# lipolski.net
KiCad netlist of a schematic drawn in EAGLE
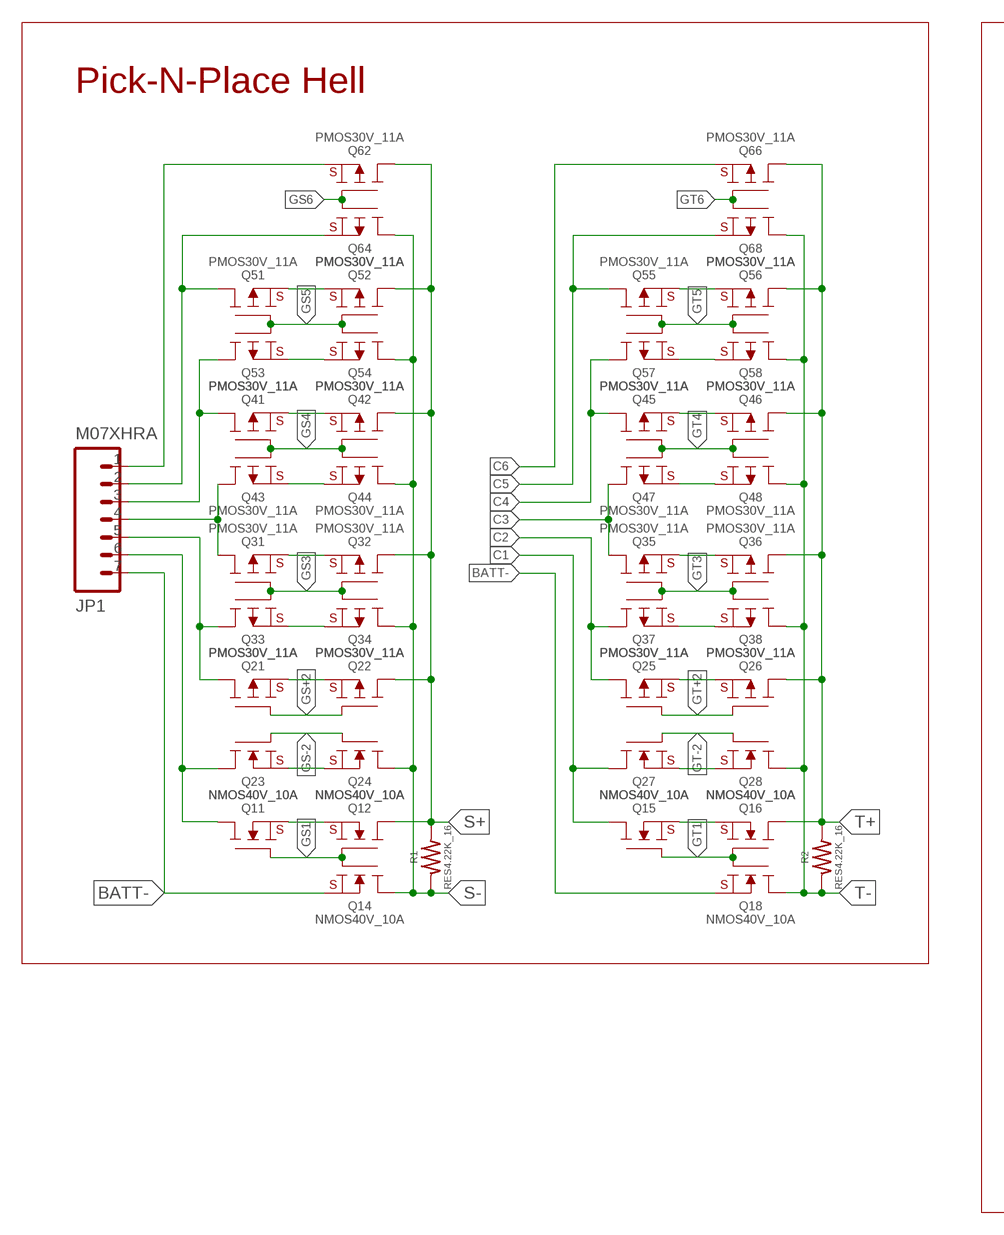
[diagram p0: schematic, sheet 1, part 1 of 2]
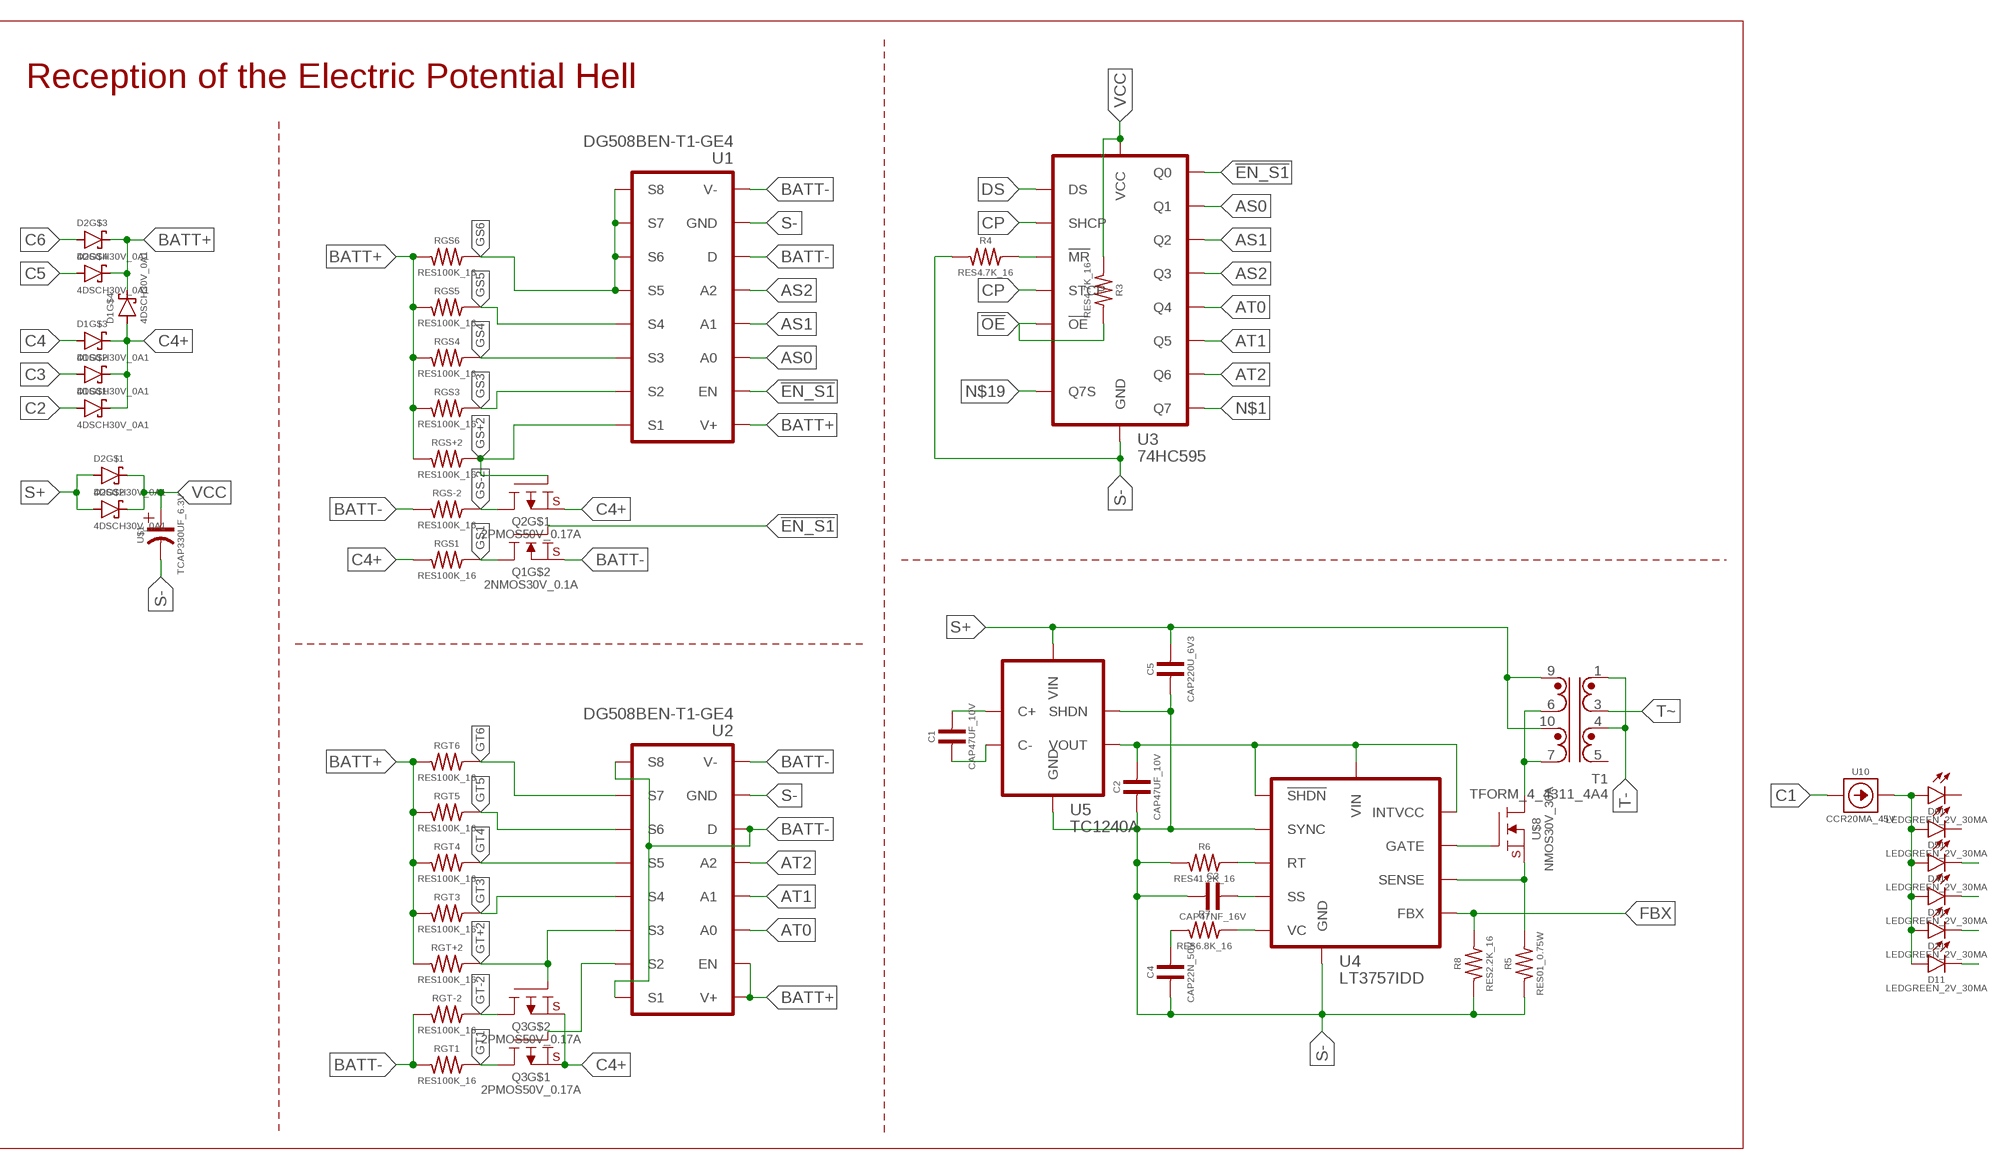
[diagram p1: schematic, sheet 1, part 2 of 2]

(export (version "E")
  (design (tool "Eeschema 10.0.6"))
  (components
    (comp (ref "C1")
      (value "CAP47UF_10V")
      (footprint "eagle-import:0805")
      (fields
        (field (name "DIGIKEY_PART_#") "445-8239-1-ND")
        (field (name "MANUFACTURER") "TDK Corporation")
        (field (name "MFG_PART_#") "C2012X5R1A476M125AC")
      )
      (libsource (lib "eagle-import") (part "CAP47UF_10V"))
    )
    (comp (ref "C2")
      (value "CAP47UF_10V")
      (footprint "eagle-import:0805")
      (fields
        (field (name "DIGIKEY_PART_#") "445-8239-1-ND")
        (field (name "MANUFACTURER") "TDK Corporation")
        (field (name "MFG_PART_#") "C2012X5R1A476M125AC")
      )
      (libsource (lib "eagle-import") (part "CAP47UF_10V"))
    )
    (comp (ref "C3")
      (value "CAP47NF_16V")
      (footprint "eagle-import:0201P")
      (fields
        (field (name "DIGIKEY_PART_#") "587-1225-1-ND")
        (field (name "MANUFACTURER") "Taiyo Yuden")
        (field (name "MFG_PART_#") "EMK105B7473KV-F")
      )
      (libsource (lib "eagle-import") (part "CAP47NF_16V"))
    )
    (comp (ref "C4")
      (value "CAP22N_50V")
      (footprint "eagle-import:0402")
      (fields
        (field (name "DIGIKEY_PART_#") "490-3884-1-ND")
        (field (name "MANUFACTURER") "Murata Electronics North America")
        (field (name "MFG_PART_#") "GRM155R71H223KA12D")
      )
      (libsource (lib "eagle-import") (part "CAP22N_50V"))
    )
    (comp (ref "C5")
      (value "CAP220U_6V3")
      (footprint "eagle-import:1210")
      (fields
        (field (name "DIGIKEY_PART_#") "1276-3375-1-ND")
        (field (name "MANUFACTURER") "Samsung Electro-Mechanics America, Inc.")
        (field (name "MFG_PART_#") "CL32A227MQVNNNE")
      )
      (libsource (lib "eagle-import") (part "CAP220U_6V3"))
    )
    (comp (ref "D1")
      (value "4DSCH30V_0A1")
      (footprint "eagle-import:8-HMD")
      (fields
        (field (name "DIGIKEY_PART_#") "RB521ZS8A30TE61CT-ND")
        (field (name "MANUFACTURER") "Rohm Semiconductor")
        (field (name "MFG_PART_#") "RB521ZS8A30TE61")
      )
      (libsource (lib "eagle-import") (part "4DSCH30V_0A1"))
    )
    (comp (ref "D2")
      (value "4DSCH30V_0A1")
      (footprint "eagle-import:8-HMD")
      (fields
        (field (name "DIGIKEY_PART_#") "RB521ZS8A30TE61CT-ND")
        (field (name "MANUFACTURER") "Rohm Semiconductor")
        (field (name "MFG_PART_#") "RB521ZS8A30TE61")
      )
      (libsource (lib "eagle-import") (part "4DSCH30V_0A1"))
    )
    (comp (ref "D11")
      (value "LEDGREEN_2V_30MA")
      (footprint "eagle-import:0603+")
      (fields
        (field (name "DIGIKEY_PART_#") "160-1435-1-ND")
        (field (name "MANUFACTURER") "Lite-On Inc.")
        (field (name "MFG_PART_#") "LTST-C190KGKT")
      )
      (libsource (lib "eagle-import") (part "LEDGREEN_2V_30MA"))
    )
    (comp (ref "D21")
      (value "LEDGREEN_2V_30MA")
      (footprint "eagle-import:0603+")
      (fields
        (field (name "DIGIKEY_PART_#") "160-1435-1-ND")
        (field (name "MANUFACTURER") "Lite-On Inc.")
        (field (name "MFG_PART_#") "LTST-C190KGKT")
      )
      (libsource (lib "eagle-import") (part "LEDGREEN_2V_30MA"))
    )
    (comp (ref "D31")
      (value "LEDGREEN_2V_30MA")
      (footprint "eagle-import:0603+")
      (fields
        (field (name "DIGIKEY_PART_#") "160-1435-1-ND")
        (field (name "MANUFACTURER") "Lite-On Inc.")
        (field (name "MFG_PART_#") "LTST-C190KGKT")
      )
      (libsource (lib "eagle-import") (part "LEDGREEN_2V_30MA"))
    )
    (comp (ref "D41")
      (value "LEDGREEN_2V_30MA")
      (footprint "eagle-import:0603+")
      (fields
        (field (name "DIGIKEY_PART_#") "160-1435-1-ND")
        (field (name "MANUFACTURER") "Lite-On Inc.")
        (field (name "MFG_PART_#") "LTST-C190KGKT")
      )
      (libsource (lib "eagle-import") (part "LEDGREEN_2V_30MA"))
    )
    (comp (ref "D51")
      (value "LEDGREEN_2V_30MA")
      (footprint "eagle-import:0603+")
      (fields
        (field (name "DIGIKEY_PART_#") "160-1435-1-ND")
        (field (name "MANUFACTURER") "Lite-On Inc.")
        (field (name "MFG_PART_#") "LTST-C190KGKT")
      )
      (libsource (lib "eagle-import") (part "LEDGREEN_2V_30MA"))
    )
    (comp (ref "D61")
      (value "LEDGREEN_2V_30MA")
      (footprint "eagle-import:0603+")
      (fields
        (field (name "DIGIKEY_PART_#") "160-1435-1-ND")
        (field (name "MANUFACTURER") "Lite-On Inc.")
        (field (name "MFG_PART_#") "LTST-C190KGKT")
      )
      (libsource (lib "eagle-import") (part "LEDGREEN_2V_30MA"))
    )
    (comp (ref "JP1")
      (value "M07XHRA")
      (footprint "eagle-import:XH07-RA")
      (fields
        (field (name "DIGIKEY_PART_#") "455-2240-ND")
        (field (name "MANUFACTURER") "JST Sales America Inc.")
        (field (name "MFG_PART_#") "S7B-XH-A(LF)(SN)")
      )
      (libsource (lib "eagle-import") (part "M07XHRA"))
    )
    (comp (ref "Q1")
      (value "2NMOS30V_0.1A")
      (footprint "eagle-import:SOT-666")
      (fields
        (field (name "DIGIKEY_PART_#") "FC6943010RCT-ND")
        (field (name "MANUFACTURER") "Panasonic Electronic Components")
        (field (name "MFG_PART_#") "FC6943010R")
      )
      (libsource (lib "eagle-import") (part "2NMOS30V_0.1A"))
    )
    (comp (ref "Q2")
      (value "2PMOS50V_0.17A")
      (footprint "eagle-import:SOT-666")
      (fields
        (field (name "DIGIKEY_PART_#") "568-10474-1-ND")
        (field (name "MANUFACTURER") "NXP Semiconductors")
        (field (name "MFG_PART_#") "BSS84AKV,115")
      )
      (libsource (lib "eagle-import") (part "2PMOS50V_0.17A"))
    )
    (comp (ref "Q3")
      (value "2PMOS50V_0.17A")
      (footprint "eagle-import:SOT-666")
      (fields
        (field (name "DIGIKEY_PART_#") "568-10474-1-ND")
        (field (name "MANUFACTURER") "NXP Semiconductors")
        (field (name "MFG_PART_#") "BSS84AKV,115")
      )
      (libsource (lib "eagle-import") (part "2PMOS50V_0.17A"))
    )
    (comp (ref "Q11")
      (value "NMOS40V_10A")
      (footprint "eagle-import:6-POWERWDFN")
      (fields
        (field (name "DIGIKEY_PART_#") "FDMA7670CT-ND")
        (field (name "MANUFACTURER") "Fairchild Semiconductor")
        (field (name "MFG_PART_#") "FDMA7670")
      )
      (libsource (lib "eagle-import") (part "NMOS40V_10A"))
    )
    (comp (ref "Q12")
      (value "NMOS40V_10A")
      (footprint "eagle-import:6-POWERWDFN")
      (fields
        (field (name "DIGIKEY_PART_#") "FDMA7670CT-ND")
        (field (name "MANUFACTURER") "Fairchild Semiconductor")
        (field (name "MFG_PART_#") "FDMA7670")
      )
      (libsource (lib "eagle-import") (part "NMOS40V_10A"))
    )
    (comp (ref "Q14")
      (value "NMOS40V_10A")
      (footprint "eagle-import:6-POWERWDFN")
      (fields
        (field (name "DIGIKEY_PART_#") "FDMA7670CT-ND")
        (field (name "MANUFACTURER") "Fairchild Semiconductor")
        (field (name "MFG_PART_#") "FDMA7670")
      )
      (libsource (lib "eagle-import") (part "NMOS40V_10A"))
    )
    (comp (ref "Q15")
      (value "NMOS40V_10A")
      (footprint "eagle-import:6-POWERWDFN")
      (fields
        (field (name "DIGIKEY_PART_#") "FDMA7670CT-ND")
        (field (name "MANUFACTURER") "Fairchild Semiconductor")
        (field (name "MFG_PART_#") "FDMA7670")
      )
      (libsource (lib "eagle-import") (part "NMOS40V_10A"))
    )
    (comp (ref "Q16")
      (value "NMOS40V_10A")
      (footprint "eagle-import:6-POWERWDFN")
      (fields
        (field (name "DIGIKEY_PART_#") "FDMA7670CT-ND")
        (field (name "MANUFACTURER") "Fairchild Semiconductor")
        (field (name "MFG_PART_#") "FDMA7670")
      )
      (libsource (lib "eagle-import") (part "NMOS40V_10A"))
    )
    (comp (ref "Q18")
      (value "NMOS40V_10A")
      (footprint "eagle-import:6-POWERWDFN")
      (fields
        (field (name "DIGIKEY_PART_#") "FDMA7670CT-ND")
        (field (name "MANUFACTURER") "Fairchild Semiconductor")
        (field (name "MFG_PART_#") "FDMA7670")
      )
      (libsource (lib "eagle-import") (part "NMOS40V_10A"))
    )
    (comp (ref "Q21")
      (value "PMOS30V_11A")
      (footprint "eagle-import:6-POWERWDFN")
      (fields
        (field (name "DIGIKEY_PART_#") "FDMA6676PZCT-ND")
        (field (name "MANUFACTURER") "Fairchild Semiconductor")
        (field (name "MFG_PART_#") "FDMA6676PZ")
      )
      (libsource (lib "eagle-import") (part "PMOS30V_11A"))
    )
    (comp (ref "Q22")
      (value "PMOS30V_11A")
      (footprint "eagle-import:6-POWERWDFN")
      (fields
        (field (name "DIGIKEY_PART_#") "FDMA6676PZCT-ND")
        (field (name "MANUFACTURER") "Fairchild Semiconductor")
        (field (name "MFG_PART_#") "FDMA6676PZ")
      )
      (libsource (lib "eagle-import") (part "PMOS30V_11A"))
    )
    (comp (ref "Q23")
      (value "NMOS40V_10A")
      (footprint "eagle-import:6-POWERWDFN")
      (fields
        (field (name "DIGIKEY_PART_#") "FDMA7670CT-ND")
        (field (name "MANUFACTURER") "Fairchild Semiconductor")
        (field (name "MFG_PART_#") "FDMA7670")
      )
      (libsource (lib "eagle-import") (part "NMOS40V_10A"))
    )
    (comp (ref "Q24")
      (value "NMOS40V_10A")
      (footprint "eagle-import:6-POWERWDFN")
      (fields
        (field (name "DIGIKEY_PART_#") "FDMA7670CT-ND")
        (field (name "MANUFACTURER") "Fairchild Semiconductor")
        (field (name "MFG_PART_#") "FDMA7670")
      )
      (libsource (lib "eagle-import") (part "NMOS40V_10A"))
    )
    (comp (ref "Q25")
      (value "PMOS30V_11A")
      (footprint "eagle-import:6-POWERWDFN")
      (fields
        (field (name "DIGIKEY_PART_#") "FDMA6676PZCT-ND")
        (field (name "MANUFACTURER") "Fairchild Semiconductor")
        (field (name "MFG_PART_#") "FDMA6676PZ")
      )
      (libsource (lib "eagle-import") (part "PMOS30V_11A"))
    )
    (comp (ref "Q26")
      (value "PMOS30V_11A")
      (footprint "eagle-import:6-POWERWDFN")
      (fields
        (field (name "DIGIKEY_PART_#") "FDMA6676PZCT-ND")
        (field (name "MANUFACTURER") "Fairchild Semiconductor")
        (field (name "MFG_PART_#") "FDMA6676PZ")
      )
      (libsource (lib "eagle-import") (part "PMOS30V_11A"))
    )
    (comp (ref "Q27")
      (value "NMOS40V_10A")
      (footprint "eagle-import:6-POWERWDFN")
      (fields
        (field (name "DIGIKEY_PART_#") "FDMA7670CT-ND")
        (field (name "MANUFACTURER") "Fairchild Semiconductor")
        (field (name "MFG_PART_#") "FDMA7670")
      )
      (libsource (lib "eagle-import") (part "NMOS40V_10A"))
    )
    (comp (ref "Q28")
      (value "NMOS40V_10A")
      (footprint "eagle-import:6-POWERWDFN")
      (fields
        (field (name "DIGIKEY_PART_#") "FDMA7670CT-ND")
        (field (name "MANUFACTURER") "Fairchild Semiconductor")
        (field (name "MFG_PART_#") "FDMA7670")
      )
      (libsource (lib "eagle-import") (part "NMOS40V_10A"))
    )
    (comp (ref "Q31")
      (value "PMOS30V_11A")
      (footprint "eagle-import:6-POWERWDFN")
      (fields
        (field (name "DIGIKEY_PART_#") "FDMA6676PZCT-ND")
        (field (name "MANUFACTURER") "Fairchild Semiconductor")
        (field (name "MFG_PART_#") "FDMA6676PZ")
      )
      (libsource (lib "eagle-import") (part "PMOS30V_11A"))
    )
    (comp (ref "Q32")
      (value "PMOS30V_11A")
      (footprint "eagle-import:6-POWERWDFN")
      (fields
        (field (name "DIGIKEY_PART_#") "FDMA6676PZCT-ND")
        (field (name "MANUFACTURER") "Fairchild Semiconductor")
        (field (name "MFG_PART_#") "FDMA6676PZ")
      )
      (libsource (lib "eagle-import") (part "PMOS30V_11A"))
    )
    (comp (ref "Q33")
      (value "PMOS30V_11A")
      (footprint "eagle-import:6-POWERWDFN")
      (fields
        (field (name "DIGIKEY_PART_#") "FDMA6676PZCT-ND")
        (field (name "MANUFACTURER") "Fairchild Semiconductor")
        (field (name "MFG_PART_#") "FDMA6676PZ")
      )
      (libsource (lib "eagle-import") (part "PMOS30V_11A"))
    )
    (comp (ref "Q34")
      (value "PMOS30V_11A")
      (footprint "eagle-import:6-POWERWDFN")
      (fields
        (field (name "DIGIKEY_PART_#") "FDMA6676PZCT-ND")
        (field (name "MANUFACTURER") "Fairchild Semiconductor")
        (field (name "MFG_PART_#") "FDMA6676PZ")
      )
      (libsource (lib "eagle-import") (part "PMOS30V_11A"))
    )
    (comp (ref "Q35")
      (value "PMOS30V_11A")
      (footprint "eagle-import:6-POWERWDFN")
      (fields
        (field (name "DIGIKEY_PART_#") "FDMA6676PZCT-ND")
        (field (name "MANUFACTURER") "Fairchild Semiconductor")
        (field (name "MFG_PART_#") "FDMA6676PZ")
      )
      (libsource (lib "eagle-import") (part "PMOS30V_11A"))
    )
    (comp (ref "Q36")
      (value "PMOS30V_11A")
      (footprint "eagle-import:6-POWERWDFN")
      (fields
        (field (name "DIGIKEY_PART_#") "FDMA6676PZCT-ND")
        (field (name "MANUFACTURER") "Fairchild Semiconductor")
        (field (name "MFG_PART_#") "FDMA6676PZ")
      )
      (libsource (lib "eagle-import") (part "PMOS30V_11A"))
    )
    (comp (ref "Q37")
      (value "PMOS30V_11A")
      (footprint "eagle-import:6-POWERWDFN")
      (fields
        (field (name "DIGIKEY_PART_#") "FDMA6676PZCT-ND")
        (field (name "MANUFACTURER") "Fairchild Semiconductor")
        (field (name "MFG_PART_#") "FDMA6676PZ")
      )
      (libsource (lib "eagle-import") (part "PMOS30V_11A"))
    )
    (comp (ref "Q38")
      (value "PMOS30V_11A")
      (footprint "eagle-import:6-POWERWDFN")
      (fields
        (field (name "DIGIKEY_PART_#") "FDMA6676PZCT-ND")
        (field (name "MANUFACTURER") "Fairchild Semiconductor")
        (field (name "MFG_PART_#") "FDMA6676PZ")
      )
      (libsource (lib "eagle-import") (part "PMOS30V_11A"))
    )
    (comp (ref "Q41")
      (value "PMOS30V_11A")
      (footprint "eagle-import:6-POWERWDFN")
      (fields
        (field (name "DIGIKEY_PART_#") "FDMA6676PZCT-ND")
        (field (name "MANUFACTURER") "Fairchild Semiconductor")
        (field (name "MFG_PART_#") "FDMA6676PZ")
      )
      (libsource (lib "eagle-import") (part "PMOS30V_11A"))
    )
    (comp (ref "Q42")
      (value "PMOS30V_11A")
      (footprint "eagle-import:6-POWERWDFN")
      (fields
        (field (name "DIGIKEY_PART_#") "FDMA6676PZCT-ND")
        (field (name "MANUFACTURER") "Fairchild Semiconductor")
        (field (name "MFG_PART_#") "FDMA6676PZ")
      )
      (libsource (lib "eagle-import") (part "PMOS30V_11A"))
    )
    (comp (ref "Q43")
      (value "PMOS30V_11A")
      (footprint "eagle-import:6-POWERWDFN")
      (fields
        (field (name "DIGIKEY_PART_#") "FDMA6676PZCT-ND")
        (field (name "MANUFACTURER") "Fairchild Semiconductor")
        (field (name "MFG_PART_#") "FDMA6676PZ")
      )
      (libsource (lib "eagle-import") (part "PMOS30V_11A"))
    )
    (comp (ref "Q44")
      (value "PMOS30V_11A")
      (footprint "eagle-import:6-POWERWDFN")
      (fields
        (field (name "DIGIKEY_PART_#") "FDMA6676PZCT-ND")
        (field (name "MANUFACTURER") "Fairchild Semiconductor")
        (field (name "MFG_PART_#") "FDMA6676PZ")
      )
      (libsource (lib "eagle-import") (part "PMOS30V_11A"))
    )
    (comp (ref "Q45")
      (value "PMOS30V_11A")
      (footprint "eagle-import:6-POWERWDFN")
      (fields
        (field (name "DIGIKEY_PART_#") "FDMA6676PZCT-ND")
        (field (name "MANUFACTURER") "Fairchild Semiconductor")
        (field (name "MFG_PART_#") "FDMA6676PZ")
      )
      (libsource (lib "eagle-import") (part "PMOS30V_11A"))
    )
    (comp (ref "Q46")
      (value "PMOS30V_11A")
      (footprint "eagle-import:6-POWERWDFN")
      (fields
        (field (name "DIGIKEY_PART_#") "FDMA6676PZCT-ND")
        (field (name "MANUFACTURER") "Fairchild Semiconductor")
        (field (name "MFG_PART_#") "FDMA6676PZ")
      )
      (libsource (lib "eagle-import") (part "PMOS30V_11A"))
    )
    (comp (ref "Q47")
      (value "PMOS30V_11A")
      (footprint "eagle-import:6-POWERWDFN")
      (fields
        (field (name "DIGIKEY_PART_#") "FDMA6676PZCT-ND")
        (field (name "MANUFACTURER") "Fairchild Semiconductor")
        (field (name "MFG_PART_#") "FDMA6676PZ")
      )
      (libsource (lib "eagle-import") (part "PMOS30V_11A"))
    )
    (comp (ref "Q48")
      (value "PMOS30V_11A")
      (footprint "eagle-import:6-POWERWDFN")
      (fields
        (field (name "DIGIKEY_PART_#") "FDMA6676PZCT-ND")
        (field (name "MANUFACTURER") "Fairchild Semiconductor")
        (field (name "MFG_PART_#") "FDMA6676PZ")
      )
      (libsource (lib "eagle-import") (part "PMOS30V_11A"))
    )
    (comp (ref "Q51")
      (value "PMOS30V_11A")
      (footprint "eagle-import:6-POWERWDFN")
      (fields
        (field (name "DIGIKEY_PART_#") "FDMA6676PZCT-ND")
        (field (name "MANUFACTURER") "Fairchild Semiconductor")
        (field (name "MFG_PART_#") "FDMA6676PZ")
      )
      (libsource (lib "eagle-import") (part "PMOS30V_11A"))
    )
    (comp (ref "Q52")
      (value "PMOS30V_11A")
      (footprint "eagle-import:6-POWERWDFN")
      (fields
        (field (name "DIGIKEY_PART_#") "FDMA6676PZCT-ND")
        (field (name "MANUFACTURER") "Fairchild Semiconductor")
        (field (name "MFG_PART_#") "FDMA6676PZ")
      )
      (libsource (lib "eagle-import") (part "PMOS30V_11A"))
    )
    (comp (ref "Q53")
      (value "PMOS30V_11A")
      (footprint "eagle-import:6-POWERWDFN")
      (fields
        (field (name "DIGIKEY_PART_#") "FDMA6676PZCT-ND")
        (field (name "MANUFACTURER") "Fairchild Semiconductor")
        (field (name "MFG_PART_#") "FDMA6676PZ")
      )
      (libsource (lib "eagle-import") (part "PMOS30V_11A"))
    )
    (comp (ref "Q54")
      (value "PMOS30V_11A")
      (footprint "eagle-import:6-POWERWDFN")
      (fields
        (field (name "DIGIKEY_PART_#") "FDMA6676PZCT-ND")
        (field (name "MANUFACTURER") "Fairchild Semiconductor")
        (field (name "MFG_PART_#") "FDMA6676PZ")
      )
      (libsource (lib "eagle-import") (part "PMOS30V_11A"))
    )
    (comp (ref "Q55")
      (value "PMOS30V_11A")
      (footprint "eagle-import:6-POWERWDFN")
      (fields
        (field (name "DIGIKEY_PART_#") "FDMA6676PZCT-ND")
        (field (name "MANUFACTURER") "Fairchild Semiconductor")
        (field (name "MFG_PART_#") "FDMA6676PZ")
      )
      (libsource (lib "eagle-import") (part "PMOS30V_11A"))
    )
    (comp (ref "Q56")
      (value "PMOS30V_11A")
      (footprint "eagle-import:6-POWERWDFN")
      (fields
        (field (name "DIGIKEY_PART_#") "FDMA6676PZCT-ND")
        (field (name "MANUFACTURER") "Fairchild Semiconductor")
        (field (name "MFG_PART_#") "FDMA6676PZ")
      )
      (libsource (lib "eagle-import") (part "PMOS30V_11A"))
    )
    (comp (ref "Q57")
      (value "PMOS30V_11A")
      (footprint "eagle-import:6-POWERWDFN")
      (fields
        (field (name "DIGIKEY_PART_#") "FDMA6676PZCT-ND")
        (field (name "MANUFACTURER") "Fairchild Semiconductor")
        (field (name "MFG_PART_#") "FDMA6676PZ")
      )
      (libsource (lib "eagle-import") (part "PMOS30V_11A"))
    )
    (comp (ref "Q58")
      (value "PMOS30V_11A")
      (footprint "eagle-import:6-POWERWDFN")
      (fields
        (field (name "DIGIKEY_PART_#") "FDMA6676PZCT-ND")
        (field (name "MANUFACTURER") "Fairchild Semiconductor")
        (field (name "MFG_PART_#") "FDMA6676PZ")
      )
      (libsource (lib "eagle-import") (part "PMOS30V_11A"))
    )
    (comp (ref "Q62")
      (value "PMOS30V_11A")
      (footprint "eagle-import:6-POWERWDFN")
      (fields
        (field (name "DIGIKEY_PART_#") "FDMA6676PZCT-ND")
        (field (name "MANUFACTURER") "Fairchild Semiconductor")
        (field (name "MFG_PART_#") "FDMA6676PZ")
      )
      (libsource (lib "eagle-import") (part "PMOS30V_11A"))
    )
    (comp (ref "Q64")
      (value "PMOS30V_11A")
      (footprint "eagle-import:6-POWERWDFN")
      (fields
        (field (name "DIGIKEY_PART_#") "FDMA6676PZCT-ND")
        (field (name "MANUFACTURER") "Fairchild Semiconductor")
        (field (name "MFG_PART_#") "FDMA6676PZ")
      )
      (libsource (lib "eagle-import") (part "PMOS30V_11A"))
    )
    (comp (ref "Q66")
      (value "PMOS30V_11A")
      (footprint "eagle-import:6-POWERWDFN")
      (fields
        (field (name "DIGIKEY_PART_#") "FDMA6676PZCT-ND")
        (field (name "MANUFACTURER") "Fairchild Semiconductor")
        (field (name "MFG_PART_#") "FDMA6676PZ")
      )
      (libsource (lib "eagle-import") (part "PMOS30V_11A"))
    )
    (comp (ref "Q68")
      (value "PMOS30V_11A")
      (footprint "eagle-import:6-POWERWDFN")
      (fields
        (field (name "DIGIKEY_PART_#") "FDMA6676PZCT-ND")
        (field (name "MANUFACTURER") "Fairchild Semiconductor")
        (field (name "MFG_PART_#") "FDMA6676PZ")
      )
      (libsource (lib "eagle-import") (part "PMOS30V_11A"))
    )
    (comp (ref "R1")
      (value "RES4.22K_16")
      (footprint "eagle-import:0402")
      (fields
        (field (name "DIGIKEY_PART_#") "541-4.22KLCT-ND")
        (field (name "MANUFACTURER") "Vishay Dale")
        (field (name "MFG_PART_#") "CRCW04024K22FKED")
      )
      (libsource (lib "eagle-import") (part "RES4.22K_16"))
    )
    (comp (ref "R2")
      (value "RES4.22K_16")
      (footprint "eagle-import:0402")
      (fields
        (field (name "DIGIKEY_PART_#") "541-4.22KLCT-ND")
        (field (name "MANUFACTURER") "Vishay Dale")
        (field (name "MFG_PART_#") "CRCW04024K22FKED")
      )
      (libsource (lib "eagle-import") (part "RES4.22K_16"))
    )
    (comp (ref "R3")
      (value "RES4.7K_16")
      (footprint "eagle-import:0402")
      (fields
        (field (name "DIGIKEY_PART_#") "541-4.70KLCT-ND")
        (field (name "MANUFACTURER") "Vishay Dale")
        (field (name "MFG_PART_#") "CRCW04024K70FKED")
      )
      (libsource (lib "eagle-import") (part "RES4.7K_16"))
    )
    (comp (ref "R4")
      (value "RES4.7K_16")
      (footprint "eagle-import:0402")
      (fields
        (field (name "DIGIKEY_PART_#") "541-4.70KLCT-ND")
        (field (name "MANUFACTURER") "Vishay Dale")
        (field (name "MFG_PART_#") "CRCW04024K70FKED")
      )
      (libsource (lib "eagle-import") (part "RES4.7K_16"))
    )
    (comp (ref "R5")
      (value "RES01_0.75W")
      (footprint "eagle-import:1206")
      (fields
        (field (name "DIGIKEY_PART_#") "408-1570-1-ND")
        (field (name "MANUFACTURER") "Susumu")
        (field (name "MFG_PART_#") "KRL1632E-M-R010-F-T5")
      )
      (libsource (lib "eagle-import") (part "RES01_0.75W"))
    )
    (comp (ref "R6")
      (value "RES41.2K_16")
      (footprint "eagle-import:0402")
      (fields
        (field (name "DIGIKEY_PART_#") "541-41.2KLCT-ND")
        (field (name "MANUFACTURER") "Vishay Dale")
        (field (name "MFG_PART_#") "CRCW040241K2FKED")
      )
      (libsource (lib "eagle-import") (part "RES41.2K_16"))
    )
    (comp (ref "R7")
      (value "RES6.8K_16")
      (footprint "eagle-import:0402")
      (fields
        (field (name "DIGIKEY_PART_#") "541-6.80KLCT-ND")
        (field (name "MANUFACTURER") "Vishay Dale")
        (field (name "MFG_PART_#") "CRCW04026K80FKED")
      )
      (libsource (lib "eagle-import") (part "RES6.8K_16"))
    )
    (comp (ref "R8")
      (value "RES2.2K_16")
      (footprint "eagle-import:0402")
      (fields
        (field (name "DIGIKEY_PART_#") "541-2.20KLCT-ND")
        (field (name "MANUFACTURER") "Vishay Dale")
        (field (name "MFG_PART_#") "CRCW04022K20FKED")
      )
      (libsource (lib "eagle-import") (part "RES2.2K_16"))
    )
    (comp (ref "RGS+2")
      (value "RES100K_16")
      (footprint "eagle-import:0402")
      (fields
        (field (name "DIGIKEY_PART_#") "541-100KLCT-ND")
        (field (name "MANUFACTURER") "Vishay Dale")
        (field (name "MFG_PART_#") "CRCW0402100KFKED")
      )
      (libsource (lib "eagle-import") (part "RES100K_16"))
    )
    (comp (ref "RGS-2")
      (value "RES100K_16")
      (footprint "eagle-import:0402")
      (fields
        (field (name "DIGIKEY_PART_#") "541-100KLCT-ND")
        (field (name "MANUFACTURER") "Vishay Dale")
        (field (name "MFG_PART_#") "CRCW0402100KFKED")
      )
      (libsource (lib "eagle-import") (part "RES100K_16"))
    )
    (comp (ref "RGS1")
      (value "RES100K_16")
      (footprint "eagle-import:0402")
      (fields
        (field (name "DIGIKEY_PART_#") "541-100KLCT-ND")
        (field (name "MANUFACTURER") "Vishay Dale")
        (field (name "MFG_PART_#") "CRCW0402100KFKED")
      )
      (libsource (lib "eagle-import") (part "RES100K_16"))
    )
    (comp (ref "RGS3")
      (value "RES100K_16")
      (footprint "eagle-import:0402")
      (fields
        (field (name "DIGIKEY_PART_#") "541-100KLCT-ND")
        (field (name "MANUFACTURER") "Vishay Dale")
        (field (name "MFG_PART_#") "CRCW0402100KFKED")
      )
      (libsource (lib "eagle-import") (part "RES100K_16"))
    )
    (comp (ref "RGS4")
      (value "RES100K_16")
      (footprint "eagle-import:0402")
      (fields
        (field (name "DIGIKEY_PART_#") "541-100KLCT-ND")
        (field (name "MANUFACTURER") "Vishay Dale")
        (field (name "MFG_PART_#") "CRCW0402100KFKED")
      )
      (libsource (lib "eagle-import") (part "RES100K_16"))
    )
    (comp (ref "RGS5")
      (value "RES100K_16")
      (footprint "eagle-import:0402")
      (fields
        (field (name "DIGIKEY_PART_#") "541-100KLCT-ND")
        (field (name "MANUFACTURER") "Vishay Dale")
        (field (name "MFG_PART_#") "CRCW0402100KFKED")
      )
      (libsource (lib "eagle-import") (part "RES100K_16"))
    )
    (comp (ref "RGS6")
      (value "RES100K_16")
      (footprint "eagle-import:0402")
      (fields
        (field (name "DIGIKEY_PART_#") "541-100KLCT-ND")
        (field (name "MANUFACTURER") "Vishay Dale")
        (field (name "MFG_PART_#") "CRCW0402100KFKED")
      )
      (libsource (lib "eagle-import") (part "RES100K_16"))
    )
    (comp (ref "RGT+2")
      (value "RES100K_16")
      (footprint "eagle-import:0402")
      (fields
        (field (name "DIGIKEY_PART_#") "541-100KLCT-ND")
        (field (name "MANUFACTURER") "Vishay Dale")
        (field (name "MFG_PART_#") "CRCW0402100KFKED")
      )
      (libsource (lib "eagle-import") (part "RES100K_16"))
    )
    (comp (ref "RGT-2")
      (value "RES100K_16")
      (footprint "eagle-import:0402")
      (fields
        (field (name "DIGIKEY_PART_#") "541-100KLCT-ND")
        (field (name "MANUFACTURER") "Vishay Dale")
        (field (name "MFG_PART_#") "CRCW0402100KFKED")
      )
      (libsource (lib "eagle-import") (part "RES100K_16"))
    )
    (comp (ref "RGT1")
      (value "RES100K_16")
      (footprint "eagle-import:0402")
      (fields
        (field (name "DIGIKEY_PART_#") "541-100KLCT-ND")
        (field (name "MANUFACTURER") "Vishay Dale")
        (field (name "MFG_PART_#") "CRCW0402100KFKED")
      )
      (libsource (lib "eagle-import") (part "RES100K_16"))
    )
    (comp (ref "RGT3")
      (value "RES100K_16")
      (footprint "eagle-import:0402")
      (fields
        (field (name "DIGIKEY_PART_#") "541-100KLCT-ND")
        (field (name "MANUFACTURER") "Vishay Dale")
        (field (name "MFG_PART_#") "CRCW0402100KFKED")
      )
      (libsource (lib "eagle-import") (part "RES100K_16"))
    )
    (comp (ref "RGT4")
      (value "RES100K_16")
      (footprint "eagle-import:0402")
      (fields
        (field (name "DIGIKEY_PART_#") "541-100KLCT-ND")
        (field (name "MANUFACTURER") "Vishay Dale")
        (field (name "MFG_PART_#") "CRCW0402100KFKED")
      )
      (libsource (lib "eagle-import") (part "RES100K_16"))
    )
    (comp (ref "RGT5")
      (value "RES100K_16")
      (footprint "eagle-import:0402")
      (fields
        (field (name "DIGIKEY_PART_#") "541-100KLCT-ND")
        (field (name "MANUFACTURER") "Vishay Dale")
        (field (name "MFG_PART_#") "CRCW0402100KFKED")
      )
      (libsource (lib "eagle-import") (part "RES100K_16"))
    )
    (comp (ref "RGT6")
      (value "RES100K_16")
      (footprint "eagle-import:0402")
      (fields
        (field (name "DIGIKEY_PART_#") "541-100KLCT-ND")
        (field (name "MANUFACTURER") "Vishay Dale")
        (field (name "MFG_PART_#") "CRCW0402100KFKED")
      )
      (libsource (lib "eagle-import") (part "RES100K_16"))
    )
    (comp (ref "T1")
      (value "TFORM_4_4311_4A4")
      (footprint "eagle-import:EPQ13")
      (fields
        (field (name "DIGIKEY_PART_#") "732-6198-1-ND")
        (field (name "MANUFACTURER") "Wurth Electronics Inc")
        (field (name "MFG_PART_#") "7491195501")
      )
      (libsource (lib "eagle-import") (part "TFORM_4_4311_4A4"))
    )
    (comp (ref "U$1")
      (value "TCAP330UF_6.3V")
      (footprint "eagle-import:1210+")
      (fields
        (field (name "DIGIKEY_PART_#") "478-8407-1-ND")
        (field (name "MANUFACTURER") "AVX Corporation")
        (field (name "MFG_PART_#") "F950J337KBAAQ2")
      )
      (libsource (lib "eagle-import") (part "TCAP330UF_6.3V"))
    )
    (comp (ref "U$8")
      (value "NMOS30V_30A")
      (footprint "eagle-import:8-POWERWDFN")
      (fields
        (field (name "DIGIKEY_PART_#") "FDMC8010ET30CT-ND")
        (field (name "MANUFACTURER") "Fairchild Semiconductor")
        (field (name "MFG_PART_#") "FDMC8010ET30")
      )
      (libsource (lib "eagle-import") (part "NMOS30V_30A"))
    )
    (comp (ref "U1")
      (value "DG508BEN-T1-GE4")
      (footprint "eagle-import:MINIQFN-16L")
      (fields
        (field (name "MANUFACTURER") "Vishay Siliconix")
        (field (name "MOUSER_PART_#") "78-DG508BEN-T1-GE4")
      )
      (libsource (lib "eagle-import") (part "DG508BEN-T1-GE4"))
    )
    (comp (ref "U2")
      (value "DG508BEN-T1-GE4")
      (footprint "eagle-import:MINIQFN-16L")
      (fields
        (field (name "MANUFACTURER") "Vishay Siliconix")
        (field (name "MOUSER_PART_#") "78-DG508BEN-T1-GE4")
      )
      (libsource (lib "eagle-import") (part "DG508BEN-T1-GE4"))
    )
    (comp (ref "U3")
      (value "74HC595")
      (footprint "eagle-import:16-VFQFN")
      (fields
        (field (name "DIGIKEY_PART_#") "568-2719-1-ND")
        (field (name "MANUFACTURER") "NXP Semiconductors")
        (field (name "MFG_PART_#") "74HC595BQ,115")
      )
      (libsource (lib "eagle-import") (part "74HC595"))
    )
    (comp (ref "U4")
      (value "LT3757IDD")
      (footprint "eagle-import:10-WFDFN")
      (fields
        (field (name "DIGIKEY_PART_#") "LT3757IDD#PBF-ND")
        (field (name "MANUFACTURER") "Linear Technology")
        (field (name "MFG_PART_#") "LT3757IDD#PBF")
      )
      (libsource (lib "eagle-import") (part "LT3757IDD"))
    )
    (comp (ref "U5")
      (value "TC1240A")
      (footprint "eagle-import:SOT-23-6")
      (fields
        (field (name "DIGIKEY_PART_#") "TC1240AECHCT-ND")
        (field (name "MANUFACTURER") "Microchip Technology")
        (field (name "MFG_PART_#") "TC1240AECHTR")
      )
      (libsource (lib "eagle-import") (part "TC1240A"))
    )
    (comp (ref "U10")
      (value "CCR20MA_45V")
      (footprint "eagle-import:SOD-123")
      (fields
        (field (name "DIGIKEY_PART_#") "NSI45020T1GOSCT-ND")
        (field (name "MANUFACTURER") "ON Semiconductor")
        (field (name "MFG_PART_#") "NSI45020T1G")
      )
      (libsource (lib "eagle-import") (part "CCR20MA_45V"))
    )
  )
  (nets
    (net (code "1") (name "/T~{}") (class "Default")
      (node (ref "T1") (pin "3") (pinfunction "2_3") (pintype "passive"))
    )
    (net (code "2") (name "/~{EN_S1}") (class "Default")
      (node (ref "Q1") (pin "5") (pinfunction "G_5") (pintype "passive"))
      (node (ref "U1") (pin "16") (pinfunction "EN_16") (pintype "passive"))
      (node (ref "U3") (pin "15") (pinfunction "Q0_15") (pintype "passive"))
    )
    (net (code "3") (name "/~{OE}") (class "Default")
      (node (ref "R3") (pin "2") (pinfunction "2_2") (pintype "passive"))
      (node (ref "U3") (pin "13") (pinfunction "~{OE}_13") (pintype "passive"))
    )
    (net (code "4") (name "AS0") (class "Default")
      (node (ref "U1") (pin "15") (pinfunction "A0_15") (pintype "passive"))
      (node (ref "U3") (pin "1") (pinfunction "Q1_1") (pintype "passive"))
    )
    (net (code "5") (name "AS1") (class "Default")
      (node (ref "U1") (pin "14") (pinfunction "A1_14") (pintype "passive"))
      (node (ref "U3") (pin "2") (pinfunction "Q2_2") (pintype "passive"))
    )
    (net (code "6") (name "AS2") (class "Default")
      (node (ref "U1") (pin "13") (pinfunction "A2_13") (pintype "passive"))
      (node (ref "U3") (pin "3") (pinfunction "Q3_3") (pintype "passive"))
    )
    (net (code "7") (name "AT0") (class "Default")
      (node (ref "U2") (pin "15") (pinfunction "A0_15") (pintype "passive"))
      (node (ref "U3") (pin "4") (pinfunction "Q4_4") (pintype "passive"))
    )
    (net (code "8") (name "AT1") (class "Default")
      (node (ref "U2") (pin "14") (pinfunction "A1_14") (pintype "passive"))
      (node (ref "U3") (pin "5") (pinfunction "Q5_5") (pintype "passive"))
    )
    (net (code "9") (name "AT2") (class "Default")
      (node (ref "U2") (pin "13") (pinfunction "A2_13") (pintype "passive"))
      (node (ref "U3") (pin "6") (pinfunction "Q6_6") (pintype "passive"))
    )
    (net (code "10") (name "BATT+") (class "Default")
      (node (ref "D1") (pin "5") (pinfunction "C_5") (pintype "passive"))
      (node (ref "D2") (pin "5") (pinfunction "C_5") (pintype "passive"))
      (node (ref "D2") (pin "6") (pinfunction "C_6") (pintype "passive"))
      (node (ref "RGS+2") (pin "1") (pinfunction "1_1") (pintype "passive"))
      (node (ref "RGS3") (pin "1") (pinfunction "1_1") (pintype "passive"))
      (node (ref "RGS4") (pin "1") (pinfunction "1_1") (pintype "passive"))
      (node (ref "RGS5") (pin "1") (pinfunction "1_1") (pintype "passive"))
      (node (ref "RGS6") (pin "1") (pinfunction "1_1") (pintype "passive"))
      (node (ref "RGT+2") (pin "1") (pinfunction "1_1") (pintype "passive"))
      (node (ref "RGT3") (pin "1") (pinfunction "1_1") (pintype "passive"))
      (node (ref "RGT4") (pin "1") (pinfunction "1_1") (pintype "passive"))
      (node (ref "RGT5") (pin "1") (pinfunction "1_1") (pintype "passive"))
      (node (ref "RGT6") (pin "1") (pinfunction "1_1") (pintype "passive"))
      (node (ref "U1") (pin "11") (pinfunction "V+_11") (pintype "passive"))
      (node (ref "U2") (pin "11") (pinfunction "V+_11") (pintype "passive"))
      (node (ref "U2") (pin "16") (pinfunction "EN_16") (pintype "passive"))
    )
    (net (code "11") (name "BATT-") (class "Default")
      (node (ref "JP1") (pin "7") (pinfunction "7_7") (pintype "passive"))
      (node (ref "Q1") (pin "4") (pinfunction "S_4") (pintype "passive"))
      (node (ref "Q14") (pin "S") (pinfunction "S_S") (pintype "passive"))
      (node (ref "Q18") (pin "S") (pinfunction "S_S") (pintype "passive"))
      (node (ref "RGS-2") (pin "1") (pinfunction "1_1") (pintype "passive"))
      (node (ref "RGT-2") (pin "1") (pinfunction "1_1") (pintype "passive"))
      (node (ref "RGT1") (pin "1") (pinfunction "1_1") (pintype "passive"))
      (node (ref "U1") (pin "1") (pinfunction "V-_1") (pintype "passive"))
      (node (ref "U1") (pin "6") (pinfunction "D_6") (pintype "passive"))
      (node (ref "U2") (pin "1") (pinfunction "V-_1") (pintype "passive"))
      (node (ref "U2") (pin "2") (pinfunction "S1_2") (pintype "passive"))
      (node (ref "U2") (pin "6") (pinfunction "D_6") (pintype "passive"))
      (node (ref "U2") (pin "7") (pinfunction "S8_7") (pintype "passive"))
    )
    (net (code "12") (name "C1") (class "Default")
      (node (ref "JP1") (pin "6") (pinfunction "6_6") (pintype "passive"))
      (node (ref "Q11") (pin "D") (pinfunction "D_D") (pintype "passive"))
      (node (ref "Q15") (pin "D") (pinfunction "D_D") (pintype "passive"))
      (node (ref "Q23") (pin "D") (pinfunction "D_D") (pintype "passive"))
      (node (ref "Q27") (pin "D") (pinfunction "D_D") (pintype "passive"))
      (node (ref "U10") (pin "A") (pinfunction "A_A") (pintype "passive"))
    )
    (net (code "13") (name "C2") (class "Default")
      (node (ref "D1") (pin "1") (pinfunction "A_1") (pintype "passive"))
      (node (ref "JP1") (pin "5") (pinfunction "5_5") (pintype "passive"))
      (node (ref "Q21") (pin "D") (pinfunction "D_D") (pintype "passive"))
      (node (ref "Q25") (pin "D") (pinfunction "D_D") (pintype "passive"))
      (node (ref "Q33") (pin "D") (pinfunction "D_D") (pintype "passive"))
      (node (ref "Q37") (pin "D") (pinfunction "D_D") (pintype "passive"))
    )
    (net (code "14") (name "C3") (class "Default")
      (node (ref "D1") (pin "2") (pinfunction "A_2") (pintype "passive"))
      (node (ref "JP1") (pin "4") (pinfunction "4_4") (pintype "passive"))
      (node (ref "Q31") (pin "D") (pinfunction "D_D") (pintype "passive"))
      (node (ref "Q35") (pin "D") (pinfunction "D_D") (pintype "passive"))
      (node (ref "Q43") (pin "D") (pinfunction "D_D") (pintype "passive"))
      (node (ref "Q47") (pin "D") (pinfunction "D_D") (pintype "passive"))
    )
    (net (code "15") (name "C4") (class "Default")
      (node (ref "D1") (pin "3") (pinfunction "A_3") (pintype "passive"))
      (node (ref "JP1") (pin "3") (pinfunction "3_3") (pintype "passive"))
      (node (ref "Q41") (pin "D") (pinfunction "D_D") (pintype "passive"))
      (node (ref "Q45") (pin "D") (pinfunction "D_D") (pintype "passive"))
      (node (ref "Q53") (pin "D") (pinfunction "D_D") (pintype "passive"))
      (node (ref "Q57") (pin "D") (pinfunction "D_D") (pintype "passive"))
    )
    (net (code "16") (name "C4+") (class "Default")
      (node (ref "D1") (pin "4") (pinfunction "A_4") (pintype "passive"))
      (node (ref "D1") (pin "6") (pinfunction "C_6") (pintype "passive"))
      (node (ref "D1") (pin "7") (pinfunction "C_7") (pintype "passive"))
      (node (ref "D1") (pin "8") (pinfunction "C_8") (pintype "passive"))
      (node (ref "Q2") (pin "1") (pinfunction "S_1") (pintype "passive"))
      (node (ref "Q3") (pin "1") (pinfunction "S_1") (pintype "passive"))
      (node (ref "Q3") (pin "4") (pinfunction "S_4") (pintype "passive"))
      (node (ref "RGS1") (pin "1") (pinfunction "1_1") (pintype "passive"))
    )
    (net (code "17") (name "C5") (class "Default")
      (node (ref "D2") (pin "4") (pinfunction "A_4") (pintype "passive"))
      (node (ref "JP1") (pin "2") (pinfunction "2_2") (pintype "passive"))
      (node (ref "Q51") (pin "D") (pinfunction "D_D") (pintype "passive"))
      (node (ref "Q55") (pin "D") (pinfunction "D_D") (pintype "passive"))
      (node (ref "Q64") (pin "S") (pinfunction "S_S") (pintype "passive"))
      (node (ref "Q68") (pin "S") (pinfunction "S_S") (pintype "passive"))
    )
    (net (code "18") (name "C6") (class "Default")
      (node (ref "D2") (pin "3") (pinfunction "A_3") (pintype "passive"))
      (node (ref "JP1") (pin "1") (pinfunction "1_1") (pintype "passive"))
      (node (ref "Q62") (pin "S") (pinfunction "S_S") (pintype "passive"))
      (node (ref "Q66") (pin "S") (pinfunction "S_S") (pintype "passive"))
    )
    (net (code "19") (name "CP") (class "Default")
      (node (ref "U3") (pin "11") (pinfunction "SHCP_11") (pintype "passive"))
      (node (ref "U3") (pin "12") (pinfunction "STCP_12") (pintype "passive"))
    )
    (net (code "20") (name "DS") (class "Default")
      (node (ref "U3") (pin "14") (pinfunction "DS_14") (pintype "passive"))
    )
    (net (code "21") (name "FBX") (class "Default")
      (node (ref "R8") (pin "2") (pinfunction "2_2") (pintype "passive"))
      (node (ref "U4") (pin "2") (pinfunction "FBX_2") (pintype "passive"))
    )
    (net (code "22") (name "GS+2") (class "Default")
      (node (ref "Q2") (pin "2") (pinfunction "G_2") (pintype "passive"))
      (node (ref "Q21") (pin "G") (pinfunction "G_G") (pintype "passive"))
      (node (ref "Q22") (pin "G") (pinfunction "G_G") (pintype "passive"))
      (node (ref "RGS+2") (pin "2") (pinfunction "2_2") (pintype "passive"))
      (node (ref "U1") (pin "2") (pinfunction "S1_2") (pintype "passive"))
    )
    (net (code "23") (name "GS-2") (class "Default")
      (node (ref "Q2") (pin "6") (pinfunction "D_6") (pintype "passive"))
      (node (ref "Q23") (pin "G") (pinfunction "G_G") (pintype "passive"))
      (node (ref "Q24") (pin "G") (pinfunction "G_G") (pintype "passive"))
      (node (ref "RGS-2") (pin "2") (pinfunction "2_2") (pintype "passive"))
    )
    (net (code "24") (name "GS1") (class "Default")
      (node (ref "Q1") (pin "3") (pinfunction "D_3") (pintype "passive"))
      (node (ref "Q11") (pin "G") (pinfunction "G_G") (pintype "passive"))
      (node (ref "Q12") (pin "G") (pinfunction "G_G") (pintype "passive"))
      (node (ref "Q14") (pin "G") (pinfunction "G_G") (pintype "passive"))
      (node (ref "RGS1") (pin "2") (pinfunction "2_2") (pintype "passive"))
    )
    (net (code "25") (name "GS3") (class "Default")
      (node (ref "Q31") (pin "G") (pinfunction "G_G") (pintype "passive"))
      (node (ref "Q32") (pin "G") (pinfunction "G_G") (pintype "passive"))
      (node (ref "Q33") (pin "G") (pinfunction "G_G") (pintype "passive"))
      (node (ref "Q34") (pin "G") (pinfunction "G_G") (pintype "passive"))
      (node (ref "RGS3") (pin "2") (pinfunction "2_2") (pintype "passive"))
      (node (ref "U1") (pin "3") (pinfunction "S2_3") (pintype "passive"))
    )
    (net (code "26") (name "GS4") (class "Default")
      (node (ref "Q41") (pin "G") (pinfunction "G_G") (pintype "passive"))
      (node (ref "Q42") (pin "G") (pinfunction "G_G") (pintype "passive"))
      (node (ref "Q43") (pin "G") (pinfunction "G_G") (pintype "passive"))
      (node (ref "Q44") (pin "G") (pinfunction "G_G") (pintype "passive"))
      (node (ref "RGS4") (pin "2") (pinfunction "2_2") (pintype "passive"))
      (node (ref "U1") (pin "4") (pinfunction "S3_4") (pintype "passive"))
    )
    (net (code "27") (name "GS5") (class "Default")
      (node (ref "Q51") (pin "G") (pinfunction "G_G") (pintype "passive"))
      (node (ref "Q52") (pin "G") (pinfunction "G_G") (pintype "passive"))
      (node (ref "Q53") (pin "G") (pinfunction "G_G") (pintype "passive"))
      (node (ref "Q54") (pin "G") (pinfunction "G_G") (pintype "passive"))
      (node (ref "RGS5") (pin "2") (pinfunction "2_2") (pintype "passive"))
      (node (ref "U1") (pin "5") (pinfunction "S4_5") (pintype "passive"))
    )
    (net (code "28") (name "GS6") (class "Default")
      (node (ref "Q62") (pin "G") (pinfunction "G_G") (pintype "passive"))
      (node (ref "Q64") (pin "G") (pinfunction "G_G") (pintype "passive"))
      (node (ref "RGS6") (pin "2") (pinfunction "2_2") (pintype "passive"))
      (node (ref "U1") (pin "10") (pinfunction "S5_10") (pintype "passive"))
      (node (ref "U1") (pin "7") (pinfunction "S8_7") (pintype "passive"))
      (node (ref "U1") (pin "8") (pinfunction "S7_8") (pintype "passive"))
      (node (ref "U1") (pin "9") (pinfunction "S6_9") (pintype "passive"))
    )
    (net (code "29") (name "GT+2") (class "Default")
      (node (ref "Q25") (pin "G") (pinfunction "G_G") (pintype "passive"))
      (node (ref "Q26") (pin "G") (pinfunction "G_G") (pintype "passive"))
      (node (ref "Q3") (pin "5") (pinfunction "G_5") (pintype "passive"))
      (node (ref "RGT+2") (pin "2") (pinfunction "2_2") (pintype "passive"))
      (node (ref "U2") (pin "4") (pinfunction "S3_4") (pintype "passive"))
    )
    (net (code "30") (name "GT-2") (class "Default")
      (node (ref "Q27") (pin "G") (pinfunction "G_G") (pintype "passive"))
      (node (ref "Q28") (pin "G") (pinfunction "G_G") (pintype "passive"))
      (node (ref "Q3") (pin "3") (pinfunction "D_3") (pintype "passive"))
      (node (ref "RGT-2") (pin "2") (pinfunction "2_2") (pintype "passive"))
    )
    (net (code "31") (name "GT1") (class "Default")
      (node (ref "Q15") (pin "G") (pinfunction "G_G") (pintype "passive"))
      (node (ref "Q16") (pin "G") (pinfunction "G_G") (pintype "passive"))
      (node (ref "Q18") (pin "G") (pinfunction "G_G") (pintype "passive"))
      (node (ref "Q3") (pin "6") (pinfunction "D_6") (pintype "passive"))
      (node (ref "RGT1") (pin "2") (pinfunction "2_2") (pintype "passive"))
    )
    (net (code "32") (name "GT3") (class "Default")
      (node (ref "Q35") (pin "G") (pinfunction "G_G") (pintype "passive"))
      (node (ref "Q36") (pin "G") (pinfunction "G_G") (pintype "passive"))
      (node (ref "Q37") (pin "G") (pinfunction "G_G") (pintype "passive"))
      (node (ref "Q38") (pin "G") (pinfunction "G_G") (pintype "passive"))
      (node (ref "RGT3") (pin "2") (pinfunction "2_2") (pintype "passive"))
      (node (ref "U2") (pin "5") (pinfunction "S4_5") (pintype "passive"))
    )
    (net (code "33") (name "GT4") (class "Default")
      (node (ref "Q45") (pin "G") (pinfunction "G_G") (pintype "passive"))
      (node (ref "Q46") (pin "G") (pinfunction "G_G") (pintype "passive"))
      (node (ref "Q47") (pin "G") (pinfunction "G_G") (pintype "passive"))
      (node (ref "Q48") (pin "G") (pinfunction "G_G") (pintype "passive"))
      (node (ref "RGT4") (pin "2") (pinfunction "2_2") (pintype "passive"))
      (node (ref "U2") (pin "10") (pinfunction "S5_10") (pintype "passive"))
    )
    (net (code "34") (name "GT5") (class "Default")
      (node (ref "Q55") (pin "G") (pinfunction "G_G") (pintype "passive"))
      (node (ref "Q56") (pin "G") (pinfunction "G_G") (pintype "passive"))
      (node (ref "Q57") (pin "G") (pinfunction "G_G") (pintype "passive"))
      (node (ref "Q58") (pin "G") (pinfunction "G_G") (pintype "passive"))
      (node (ref "RGT5") (pin "2") (pinfunction "2_2") (pintype "passive"))
      (node (ref "U2") (pin "9") (pinfunction "S6_9") (pintype "passive"))
    )
    (net (code "35") (name "GT6") (class "Default")
      (node (ref "Q66") (pin "G") (pinfunction "G_G") (pintype "passive"))
      (node (ref "Q68") (pin "G") (pinfunction "G_G") (pintype "passive"))
      (node (ref "RGT6") (pin "2") (pinfunction "2_2") (pintype "passive"))
      (node (ref "U2") (pin "8") (pinfunction "S7_8") (pintype "passive"))
    )
    (net (code "36") (name "N$1") (class "Default")
      (node (ref "U3") (pin "7") (pinfunction "Q7_7") (pintype "passive"))
    )
    (net (code "37") (name "N$19") (class "Default")
      (node (ref "U3") (pin "9") (pinfunction "Q7S_9") (pintype "passive"))
    )
    (net (code "38") (name "Net-(C4-Pad2)") (class "Default")
      (node (ref "C4") (pin "2") (pinfunction "2_2") (pintype "passive"))
      (node (ref "R7") (pin "1") (pinfunction "1_1") (pintype "passive"))
    )
    (net (code "39") (name "Net-(D11-PadA)") (class "Default")
      (node (ref "D11") (pin "A") (pinfunction "A_A") (pintype "passive"))
      (node (ref "D21") (pin "A") (pinfunction "A_A") (pintype "passive"))
      (node (ref "D31") (pin "A") (pinfunction "A_A") (pintype "passive"))
      (node (ref "D41") (pin "A") (pinfunction "A_A") (pintype "passive"))
      (node (ref "D51") (pin "A") (pinfunction "A_A") (pintype "passive"))
      (node (ref "D61") (pin "A") (pinfunction "A_A") (pintype "passive"))
      (node (ref "U10") (pin "C") (pinfunction "C_C") (pintype "passive"))
    )
    (net (code "40") (name "Net-(Q3A-G)") (class "Default")
      (node (ref "Q3") (pin "2") (pinfunction "G_2") (pintype "passive"))
      (node (ref "U2") (pin "3") (pinfunction "S2_3") (pintype "passive"))
    )
    (net (code "41") (name "Net-(Q11-PadS)") (class "Default")
      (node (ref "Q11") (pin "S") (pinfunction "S_S") (pintype "passive"))
      (node (ref "Q12") (pin "S") (pinfunction "S_S") (pintype "passive"))
    )
    (net (code "42") (name "Net-(Q15-PadS)") (class "Default")
      (node (ref "Q15") (pin "S") (pinfunction "S_S") (pintype "passive"))
      (node (ref "Q16") (pin "S") (pinfunction "S_S") (pintype "passive"))
    )
    (net (code "43") (name "Net-(Q21-PadS)") (class "Default")
      (node (ref "Q21") (pin "S") (pinfunction "S_S") (pintype "passive"))
      (node (ref "Q22") (pin "S") (pinfunction "S_S") (pintype "passive"))
    )
    (net (code "44") (name "Net-(Q23-PadS)") (class "Default")
      (node (ref "Q23") (pin "S") (pinfunction "S_S") (pintype "passive"))
      (node (ref "Q24") (pin "S") (pinfunction "S_S") (pintype "passive"))
    )
    (net (code "45") (name "Net-(Q25-PadS)") (class "Default")
      (node (ref "Q25") (pin "S") (pinfunction "S_S") (pintype "passive"))
      (node (ref "Q26") (pin "S") (pinfunction "S_S") (pintype "passive"))
    )
    (net (code "46") (name "Net-(Q27-PadS)") (class "Default")
      (node (ref "Q27") (pin "S") (pinfunction "S_S") (pintype "passive"))
      (node (ref "Q28") (pin "S") (pinfunction "S_S") (pintype "passive"))
    )
    (net (code "47") (name "Net-(Q31-PadS)") (class "Default")
      (node (ref "Q31") (pin "S") (pinfunction "S_S") (pintype "passive"))
      (node (ref "Q32") (pin "S") (pinfunction "S_S") (pintype "passive"))
    )
    (net (code "48") (name "Net-(Q33-PadS)") (class "Default")
      (node (ref "Q33") (pin "S") (pinfunction "S_S") (pintype "passive"))
      (node (ref "Q34") (pin "S") (pinfunction "S_S") (pintype "passive"))
    )
    (net (code "49") (name "Net-(Q35-PadS)") (class "Default")
      (node (ref "Q35") (pin "S") (pinfunction "S_S") (pintype "passive"))
      (node (ref "Q36") (pin "S") (pinfunction "S_S") (pintype "passive"))
    )
    (net (code "50") (name "Net-(Q37-PadS)") (class "Default")
      (node (ref "Q37") (pin "S") (pinfunction "S_S") (pintype "passive"))
      (node (ref "Q38") (pin "S") (pinfunction "S_S") (pintype "passive"))
    )
    (net (code "51") (name "Net-(Q41-PadS)") (class "Default")
      (node (ref "Q41") (pin "S") (pinfunction "S_S") (pintype "passive"))
      (node (ref "Q42") (pin "S") (pinfunction "S_S") (pintype "passive"))
    )
    (net (code "52") (name "Net-(Q43-PadS)") (class "Default")
      (node (ref "Q43") (pin "S") (pinfunction "S_S") (pintype "passive"))
      (node (ref "Q44") (pin "S") (pinfunction "S_S") (pintype "passive"))
    )
    (net (code "53") (name "Net-(Q45-PadS)") (class "Default")
      (node (ref "Q45") (pin "S") (pinfunction "S_S") (pintype "passive"))
      (node (ref "Q46") (pin "S") (pinfunction "S_S") (pintype "passive"))
    )
    (net (code "54") (name "Net-(Q47-PadS)") (class "Default")
      (node (ref "Q47") (pin "S") (pinfunction "S_S") (pintype "passive"))
      (node (ref "Q48") (pin "S") (pinfunction "S_S") (pintype "passive"))
    )
    (net (code "55") (name "Net-(Q51-PadS)") (class "Default")
      (node (ref "Q51") (pin "S") (pinfunction "S_S") (pintype "passive"))
      (node (ref "Q52") (pin "S") (pinfunction "S_S") (pintype "passive"))
    )
    (net (code "56") (name "Net-(Q53-PadS)") (class "Default")
      (node (ref "Q53") (pin "S") (pinfunction "S_S") (pintype "passive"))
      (node (ref "Q54") (pin "S") (pinfunction "S_S") (pintype "passive"))
    )
    (net (code "57") (name "Net-(Q55-PadS)") (class "Default")
      (node (ref "Q55") (pin "S") (pinfunction "S_S") (pintype "passive"))
      (node (ref "Q56") (pin "S") (pinfunction "S_S") (pintype "passive"))
    )
    (net (code "58") (name "Net-(Q57-PadS)") (class "Default")
      (node (ref "Q57") (pin "S") (pinfunction "S_S") (pintype "passive"))
      (node (ref "Q58") (pin "S") (pinfunction "S_S") (pintype "passive"))
    )
    (net (code "59") (name "Net-(T1-5)") (class "Default")
      (node (ref "T1") (pin "6") (pinfunction "7_6") (pintype "passive"))
      (node (ref "T1") (pin "7") (pinfunction "5_7") (pintype "passive"))
      (node (ref "U$8") (pin "D") (pinfunction "D_D") (pintype "passive"))
    )
    (net (code "60") (name "Net-(U3-~{MR})") (class "Default")
      (node (ref "R4") (pin "2") (pinfunction "2_2") (pintype "passive"))
      (node (ref "U3") (pin "10") (pinfunction "~{MR}_10") (pintype "passive"))
    )
    (net (code "61") (name "Net-(U4-GATE)") (class "Default")
      (node (ref "U$8") (pin "G") (pinfunction "G_G") (pintype "passive"))
      (node (ref "U4") (pin "7") (pinfunction "GATE_7") (pintype "passive"))
    )
    (net (code "62") (name "Net-(U4-INTVCC)") (class "Default")
      (node (ref "C2") (pin "2") (pinfunction "2_2") (pintype "passive"))
      (node (ref "U4") (pin "10") (pinfunction "VIN_10") (pintype "power_in"))
      (node (ref "U4") (pin "8") (pinfunction "INTVCC_8") (pintype "passive"))
      (node (ref "U4") (pin "9") (pinfunction "~{SHDN}_9") (pintype "passive"))
      (node (ref "U5") (pin "5") (pinfunction "VOUT_5") (pintype "power_in"))
    )
    (net (code "63") (name "Net-(U4-RT)") (class "Default")
      (node (ref "R6") (pin "2") (pinfunction "2_2") (pintype "passive"))
      (node (ref "U4") (pin "4") (pinfunction "RT_4") (pintype "passive"))
    )
    (net (code "64") (name "Net-(U4-SENSE)") (class "Default")
      (node (ref "R5") (pin "2") (pinfunction "2_2") (pintype "passive"))
      (node (ref "U$8") (pin "S") (pinfunction "S_S") (pintype "passive"))
      (node (ref "U4") (pin "6") (pinfunction "SENSE_6") (pintype "passive"))
    )
    (net (code "65") (name "Net-(U4-SS)") (class "Default")
      (node (ref "C3") (pin "2") (pinfunction "2_2") (pintype "passive"))
      (node (ref "U4") (pin "3") (pinfunction "SS_3") (pintype "passive"))
    )
    (net (code "66") (name "Net-(U4-VC)") (class "Default")
      (node (ref "R7") (pin "2") (pinfunction "2_2") (pintype "passive"))
      (node (ref "U4") (pin "1") (pinfunction "VC_1") (pintype "passive"))
    )
    (net (code "67") (name "Net-(U5-C+)") (class "Default")
      (node (ref "C1") (pin "2") (pinfunction "2_2") (pintype "passive"))
      (node (ref "U5") (pin "6") (pinfunction "C+_6") (pintype "passive"))
    )
    (net (code "68") (name "Net-(U5-C-)") (class "Default")
      (node (ref "C1") (pin "1") (pinfunction "1_1") (pintype "passive"))
      (node (ref "U5") (pin "3") (pinfunction "C-_3") (pintype "passive"))
    )
    (net (code "69") (name "S+") (class "Default")
      (node (ref "C5") (pin "2") (pinfunction "2_2") (pintype "passive"))
      (node (ref "D2") (pin "1") (pinfunction "A_1") (pintype "passive"))
      (node (ref "D2") (pin "2") (pinfunction "A_2") (pintype "passive"))
      (node (ref "Q12") (pin "D") (pinfunction "D_D") (pintype "passive"))
      (node (ref "Q22") (pin "D") (pinfunction "D_D") (pintype "passive"))
      (node (ref "Q32") (pin "D") (pinfunction "D_D") (pintype "passive"))
      (node (ref "Q42") (pin "D") (pinfunction "D_D") (pintype "passive"))
      (node (ref "Q52") (pin "D") (pinfunction "D_D") (pintype "passive"))
      (node (ref "Q62") (pin "D") (pinfunction "D_D") (pintype "passive"))
      (node (ref "R1") (pin "2") (pinfunction "2_2") (pintype "passive"))
      (node (ref "T1") (pin "10") (pinfunction "6_10") (pintype "passive"))
      (node (ref "T1") (pin "9") (pinfunction "8_9") (pintype "passive"))
      (node (ref "U5") (pin "1") (pinfunction "VIN_1") (pintype "power_in"))
    )
    (net (code "70") (name "S-") (class "Default")
      (node (ref "C2") (pin "1") (pinfunction "1_1") (pintype "passive"))
      (node (ref "C3") (pin "1") (pinfunction "1_1") (pintype "passive"))
      (node (ref "C4") (pin "1") (pinfunction "1_1") (pintype "passive"))
      (node (ref "C5") (pin "1") (pinfunction "1_1") (pintype "passive"))
      (node (ref "Q14") (pin "D") (pinfunction "D_D") (pintype "passive"))
      (node (ref "Q24") (pin "D") (pinfunction "D_D") (pintype "passive"))
      (node (ref "Q34") (pin "D") (pinfunction "D_D") (pintype "passive"))
      (node (ref "Q44") (pin "D") (pinfunction "D_D") (pintype "passive"))
      (node (ref "Q54") (pin "D") (pinfunction "D_D") (pintype "passive"))
      (node (ref "Q64") (pin "D") (pinfunction "D_D") (pintype "passive"))
      (node (ref "R1") (pin "1") (pinfunction "1_1") (pintype "passive"))
      (node (ref "R4") (pin "1") (pinfunction "1_1") (pintype "passive"))
      (node (ref "R5") (pin "1") (pinfunction "1_1") (pintype "passive"))
      (node (ref "R6") (pin "1") (pinfunction "1_1") (pintype "passive"))
      (node (ref "R8") (pin "1") (pinfunction "1_1") (pintype "passive"))
      (node (ref "U$1") (pin "C") (pinfunction "C_C") (pintype "passive"))
      (node (ref "U1") (pin "12") (pinfunction "GND_12") (pintype "passive"))
      (node (ref "U2") (pin "12") (pinfunction "GND_12") (pintype "passive"))
      (node (ref "U3") (pin "8") (pinfunction "GND_8") (pintype "passive"))
      (node (ref "U3") (pin "PAD") (pinfunction "GND_PAD") (pintype "passive"))
      (node (ref "U4") (pin "5") (pinfunction "SYNC_5") (pintype "passive"))
      (node (ref "U4") (pin "PAD") (pinfunction "GND_PAD") (pintype "power_in"))
      (node (ref "U5") (pin "2") (pinfunction "GND_2") (pintype "power_in"))
      (node (ref "U5") (pin "4") (pinfunction "SHDN_4") (pintype "passive"))
    )
    (net (code "71") (name "T+") (class "Default")
      (node (ref "Q16") (pin "D") (pinfunction "D_D") (pintype "passive"))
      (node (ref "Q26") (pin "D") (pinfunction "D_D") (pintype "passive"))
      (node (ref "Q36") (pin "D") (pinfunction "D_D") (pintype "passive"))
      (node (ref "Q46") (pin "D") (pinfunction "D_D") (pintype "passive"))
      (node (ref "Q56") (pin "D") (pinfunction "D_D") (pintype "passive"))
      (node (ref "Q66") (pin "D") (pinfunction "D_D") (pintype "passive"))
      (node (ref "R2") (pin "2") (pinfunction "2_2") (pintype "passive"))
    )
    (net (code "72") (name "T-") (class "Default")
      (node (ref "Q18") (pin "D") (pinfunction "D_D") (pintype "passive"))
      (node (ref "Q28") (pin "D") (pinfunction "D_D") (pintype "passive"))
      (node (ref "Q38") (pin "D") (pinfunction "D_D") (pintype "passive"))
      (node (ref "Q48") (pin "D") (pinfunction "D_D") (pintype "passive"))
      (node (ref "Q58") (pin "D") (pinfunction "D_D") (pintype "passive"))
      (node (ref "Q68") (pin "D") (pinfunction "D_D") (pintype "passive"))
      (node (ref "R2") (pin "1") (pinfunction "1_1") (pintype "passive"))
      (node (ref "T1") (pin "1") (pinfunction "1_1") (pintype "passive"))
      (node (ref "T1") (pin "4") (pinfunction "3_4") (pintype "passive"))
    )
    (net (code "73") (name "VCC") (class "Default")
      (node (ref "D2") (pin "7") (pinfunction "C_7") (pintype "passive"))
      (node (ref "D2") (pin "8") (pinfunction "C_8") (pintype "passive"))
      (node (ref "R3") (pin "1") (pinfunction "1_1") (pintype "passive"))
      (node (ref "U$1") (pin "A") (pinfunction "A_A") (pintype "passive"))
      (node (ref "U3") (pin "16") (pinfunction "VCC_16") (pintype "passive"))
    )
    (net (code "74") (name "unconnected-(D11-PadC)") (class "Default")
      (node (ref "D11") (pin "C") (pinfunction "C_C") (pintype "passive"))
    )
    (net (code "75") (name "unconnected-(D21-PadC)") (class "Default")
      (node (ref "D21") (pin "C") (pinfunction "C_C") (pintype "passive"))
    )
    (net (code "76") (name "unconnected-(D31-PadC)") (class "Default")
      (node (ref "D31") (pin "C") (pinfunction "C_C") (pintype "passive"))
    )
    (net (code "77") (name "unconnected-(D41-PadC)") (class "Default")
      (node (ref "D41") (pin "C") (pinfunction "C_C") (pintype "passive"))
    )
    (net (code "78") (name "unconnected-(D51-PadC)") (class "Default")
      (node (ref "D51") (pin "C") (pinfunction "C_C") (pintype "passive"))
    )
    (net (code "79") (name "unconnected-(D61-PadC)") (class "Default")
      (node (ref "D61") (pin "C") (pinfunction "C_C") (pintype "passive"))
    )
    (net (code "80") (name "unconnected-(T1-4-Pad5)") (class "Default")
      (node (ref "T1") (pin "5") (pinfunction "4_5") (pintype "passive"))
    )
  )
)
